# sensors.net
KiCad netlist of a schematic drawn in EAGLE
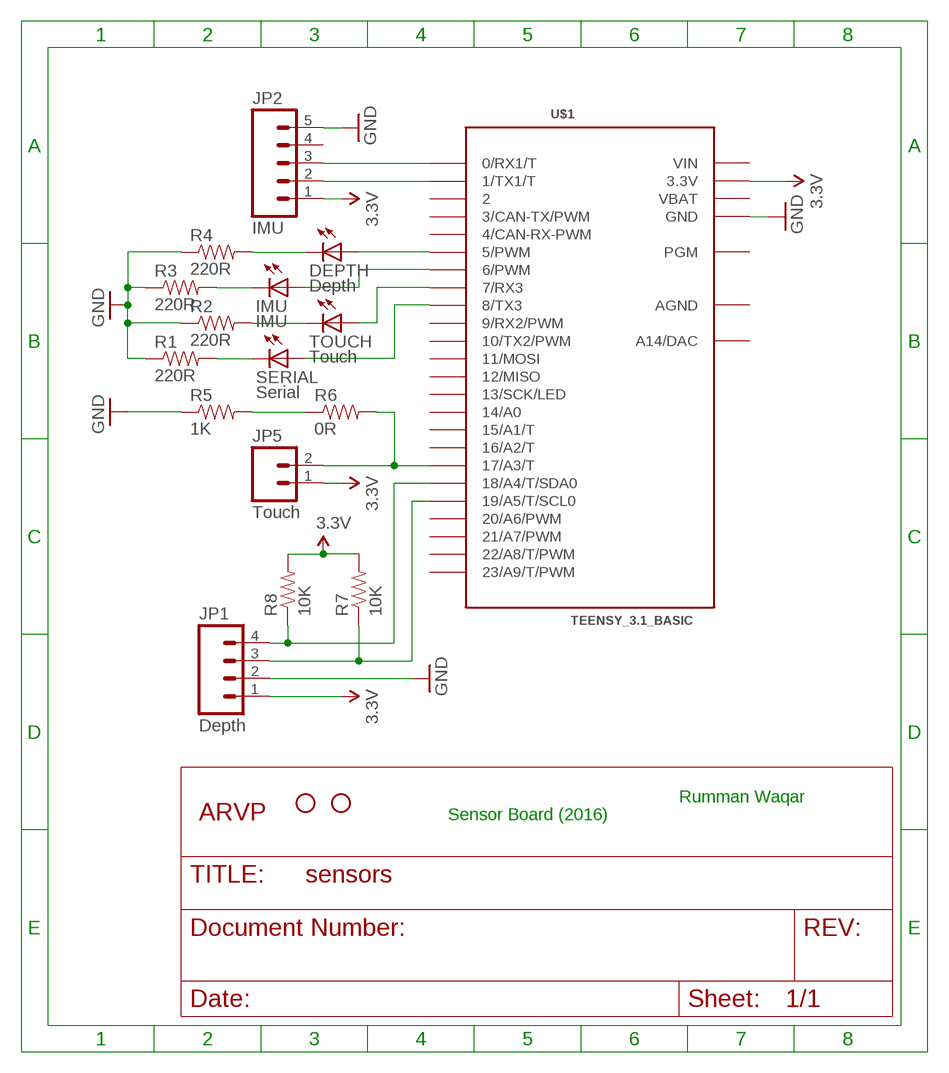
[diagram p0: schematic, sheet 1]

(export (version "E")
  (design (tool "Eeschema 10.0.6"))
  (components
    (comp (ref "DEPTH")
      (value "Depth")
      (footprint "eagle-import:LED-1206")
      (libsource (lib "eagle-import") (part "LED1206"))
    )
    (comp (ref "IMU")
      (value "IMU")
      (footprint "eagle-import:LED-1206")
      (libsource (lib "eagle-import") (part "LED1206"))
    )
    (comp (ref "JP1")
      (value "Depth")
      (footprint "eagle-import:1X04_LONGPADS")
      (libsource (lib "eagle-import") (part "M04LONGPADS"))
    )
    (comp (ref "JP2")
      (value "IMU")
      (footprint "eagle-import:1X05_LONGPADS")
      (libsource (lib "eagle-import") (part "M05PTH_LONGPADS"))
    )
    (comp (ref "JP3")
      (value "STAND-OFF")
      (footprint "eagle-import:STAND-OFF")
      (libsource (lib "eagle-import") (part "STAND-OFF"))
    )
    (comp (ref "JP4")
      (value "STAND-OFF")
      (footprint "eagle-import:STAND-OFF")
      (libsource (lib "eagle-import") (part "STAND-OFF"))
    )
    (comp (ref "JP5")
      (value "Touch")
      (footprint "eagle-import:MOLEX-1X2")
      (libsource (lib "eagle-import") (part "M02POLAR"))
    )
    (comp (ref "R1")
      (value "220R")
      (footprint "eagle-import:1206")
      (libsource (lib "eagle-import") (part "RESISTOR1206"))
    )
    (comp (ref "R2")
      (value "220R")
      (footprint "eagle-import:1206")
      (libsource (lib "eagle-import") (part "RESISTOR1206"))
    )
    (comp (ref "R3")
      (value "220R")
      (footprint "eagle-import:1206")
      (libsource (lib "eagle-import") (part "RESISTOR1206"))
    )
    (comp (ref "R4")
      (value "220R")
      (footprint "eagle-import:1206")
      (libsource (lib "eagle-import") (part "RESISTOR1206"))
    )
    (comp (ref "R5")
      (value "1K")
      (footprint "eagle-import:1206")
      (libsource (lib "eagle-import") (part "RESISTOR1206"))
    )
    (comp (ref "R6")
      (value "0R")
      (footprint "eagle-import:1206")
      (libsource (lib "eagle-import") (part "RESISTOR1206"))
    )
    (comp (ref "R7")
      (value "10K")
      (footprint "eagle-import:0805")
      (libsource (lib "eagle-import") (part "RESISTOR0805-RES"))
    )
    (comp (ref "R8")
      (value "10K")
      (footprint "eagle-import:0805")
      (libsource (lib "eagle-import") (part "RESISTOR0805-RES"))
    )
    (comp (ref "SERIAL")
      (value "Serial")
      (footprint "eagle-import:LED-1206")
      (libsource (lib "eagle-import") (part "LED1206"))
    )
    (comp (ref "TOUCH")
      (value "Touch")
      (footprint "eagle-import:LED-1206")
      (libsource (lib "eagle-import") (part "LED1206"))
    )
    (comp (ref "U$1")
      (value "TEENSY_3.1_BASIC")
      (footprint "eagle-import:TEENSY_3.1_BASIC")
      (libsource (lib "eagle-import") (part "TEENSY_3.1_BASIC"))
    )
    (comp (ref "U$2")
      (value "ARVP_LOGO")
      (footprint "eagle-import:ARVP")
      (libsource (lib "eagle-import") (part "ARVP_LOGO"))
    )
  )
  (nets
    (net (code "1") (name "/AGND") (class "Default")
      (node (ref "U$1") (pin "AGND") (pinfunction "AGND_AGND") (pintype "power_in"))
    )
    (net (code "2") (name "/VBAT") (class "Default")
      (node (ref "U$1") (pin "VBAT") (pinfunction "VBAT_VBAT") (pintype "power_in"))
    )
    (net (code "3") (name "/VIN") (class "Default")
      (node (ref "U$1") (pin "VIN") (pinfunction "VIN_VIN") (pintype "power_in"))
    )
    (net (code "4") (name "3.3V") (class "Default")
      (node (ref "JP1") (pin "1") (pinfunction "1_1") (pintype "passive"))
      (node (ref "JP2") (pin "1") (pinfunction "1_1") (pintype "passive"))
      (node (ref "JP5") (pin "1") (pinfunction "1_1") (pintype "passive"))
      (node (ref "R7") (pin "2") (pinfunction "2_2") (pintype "passive"))
      (node (ref "R8") (pin "2") (pinfunction "2_2") (pintype "passive"))
      (node (ref "U$1") (pin "3.3V") (pinfunction "3.3V_3.3V") (pintype "power_in"))
      (node (ref "U$1") (pin "3.3V1") (pinfunction "3.3V_3.3V1") (pintype "power_in"))
    )
    (net (code "5") (name "GND") (class "Default")
      (node (ref "JP1") (pin "2") (pinfunction "2_2") (pintype "passive"))
      (node (ref "JP2") (pin "5") (pinfunction "5_5") (pintype "passive"))
      (node (ref "R1") (pin "1") (pinfunction "1_1") (pintype "passive"))
      (node (ref "R2") (pin "1") (pinfunction "1_1") (pintype "passive"))
      (node (ref "R3") (pin "1") (pinfunction "1_1") (pintype "passive"))
      (node (ref "R4") (pin "1") (pinfunction "1_1") (pintype "passive"))
      (node (ref "R5") (pin "1") (pinfunction "1_1") (pintype "passive"))
      (node (ref "U$1") (pin "GND") (pinfunction "GND_GND") (pintype "power_in"))
      (node (ref "U$1") (pin "GND1") (pinfunction "GND_GND1") (pintype "power_in"))
    )
    (net (code "6") (name "Net-(DEPTH-PadC)") (class "Default")
      (node (ref "DEPTH") (pin "C") (pinfunction "C_C") (pintype "passive"))
      (node (ref "R4") (pin "2") (pinfunction "2_2") (pintype "passive"))
    )
    (net (code "7") (name "Net-(IMU-PadC)") (class "Default")
      (node (ref "IMU") (pin "C") (pinfunction "C_C") (pintype "passive"))
      (node (ref "R3") (pin "2") (pinfunction "2_2") (pintype "passive"))
    )
    (net (code "8") (name "Net-(R1-Pad2)") (class "Default")
      (node (ref "R1") (pin "2") (pinfunction "2_2") (pintype "passive"))
      (node (ref "SERIAL") (pin "C") (pinfunction "C_C") (pintype "passive"))
    )
    (net (code "9") (name "Net-(R2-Pad2)") (class "Default")
      (node (ref "R2") (pin "2") (pinfunction "2_2") (pintype "passive"))
      (node (ref "TOUCH") (pin "C") (pinfunction "C_C") (pintype "passive"))
    )
    (net (code "10") (name "Net-(R5-Pad2)") (class "Default")
      (node (ref "R5") (pin "2") (pinfunction "2_2") (pintype "passive"))
      (node (ref "R6") (pin "1") (pinfunction "1_1") (pintype "passive"))
    )
    (net (code "11") (name "Net-(U$1-0{slash}RX1{slash}T)") (class "Default")
      (node (ref "JP2") (pin "3") (pinfunction "3_3") (pintype "passive"))
      (node (ref "U$1") (pin "0") (pinfunction "0/RX1/T_0") (pintype "bidirectional"))
    )
    (net (code "12") (name "Net-(U$1-1{slash}TX1{slash}T)") (class "Default")
      (node (ref "JP2") (pin "2") (pinfunction "2_2") (pintype "passive"))
      (node (ref "U$1") (pin "1") (pinfunction "1/TX1/T_1") (pintype "bidirectional"))
    )
    (net (code "13") (name "Net-(U$1-5{slash}PWM)") (class "Default")
      (node (ref "DEPTH") (pin "A") (pinfunction "A_A") (pintype "passive"))
      (node (ref "U$1") (pin "5") (pinfunction "5/PWM_5") (pintype "bidirectional"))
    )
    (net (code "14") (name "Net-(U$1-6{slash}PWM)") (class "Default")
      (node (ref "IMU") (pin "A") (pinfunction "A_A") (pintype "passive"))
      (node (ref "U$1") (pin "6") (pinfunction "6/PWM_6") (pintype "bidirectional"))
    )
    (net (code "15") (name "Net-(U$1-7{slash}RX3)") (class "Default")
      (node (ref "TOUCH") (pin "A") (pinfunction "A_A") (pintype "passive"))
      (node (ref "U$1") (pin "7") (pinfunction "7/RX3_7") (pintype "bidirectional"))
    )
    (net (code "16") (name "Net-(U$1-8{slash}TX3)") (class "Default")
      (node (ref "SERIAL") (pin "A") (pinfunction "A_A") (pintype "passive"))
      (node (ref "U$1") (pin "8") (pinfunction "8/TX3_8") (pintype "bidirectional"))
    )
    (net (code "17") (name "Net-(U$1-17{slash}A3{slash}T)") (class "Default")
      (node (ref "JP5") (pin "2") (pinfunction "2_2") (pintype "passive"))
      (node (ref "R6") (pin "2") (pinfunction "2_2") (pintype "passive"))
      (node (ref "U$1") (pin "17/A3") (pinfunction "17/A3/T_17/A3") (pintype "bidirectional"))
    )
    (net (code "18") (name "Net-(U$1-18{slash}A4{slash}T{slash}SDA0)") (class "Default")
      (node (ref "JP1") (pin "4") (pinfunction "4_4") (pintype "passive"))
      (node (ref "R8") (pin "1") (pinfunction "1_1") (pintype "passive"))
      (node (ref "U$1") (pin "18/A4") (pinfunction "18/A4/T/SDA0_18/A4") (pintype "bidirectional"))
    )
    (net (code "19") (name "Net-(U$1-19{slash}A5{slash}T{slash}SCL0)") (class "Default")
      (node (ref "JP1") (pin "3") (pinfunction "3_3") (pintype "passive"))
      (node (ref "R7") (pin "1") (pinfunction "1_1") (pintype "passive"))
      (node (ref "U$1") (pin "19/A5") (pinfunction "19/A5/T/SCL0_19/A5") (pintype "bidirectional"))
    )
    (net (code "20") (name "unconnected-(JP2-Pad4)") (class "Default")
      (node (ref "JP2") (pin "4") (pinfunction "4_4") (pintype "passive"))
    )
    (net (code "21") (name "unconnected-(U$1-3{slash}CAN-TX{slash}PWM-Pad3)") (class "Default")
      (node (ref "U$1") (pin "3") (pinfunction "3/CAN-TX/PWM_3") (pintype "bidirectional"))
    )
    (net (code "22") (name "unconnected-(U$1-4{slash}CAN-RX-PWM-Pad4)") (class "Default")
      (node (ref "U$1") (pin "4") (pinfunction "4/CAN-RX-PWM_4") (pintype "bidirectional"))
    )
    (net (code "23") (name "unconnected-(U$1-9{slash}RX2{slash}PWM-Pad9)") (class "Default")
      (node (ref "U$1") (pin "9") (pinfunction "9/RX2/PWM_9") (pintype "bidirectional"))
    )
    (net (code "24") (name "unconnected-(U$1-10{slash}TX2{slash}PWM-Pad10)") (class "Default")
      (node (ref "U$1") (pin "10") (pinfunction "10/TX2/PWM_10") (pintype "bidirectional"))
    )
    (net (code "25") (name "unconnected-(U$1-11{slash}MOSI-Pad11)") (class "Default")
      (node (ref "U$1") (pin "11") (pinfunction "11/MOSI_11") (pintype "bidirectional"))
    )
    (net (code "26") (name "unconnected-(U$1-12{slash}MISO-Pad12)") (class "Default")
      (node (ref "U$1") (pin "12") (pinfunction "12/MISO_12") (pintype "bidirectional"))
    )
    (net (code "27") (name "unconnected-(U$1-13{slash}SCK{slash}LED-Pad13)") (class "Default")
      (node (ref "U$1") (pin "13") (pinfunction "13/SCK/LED_13") (pintype "bidirectional"))
    )
    (net (code "28") (name "unconnected-(U$1-15{slash}A1{slash}T-Pad15{slash}A1)") (class "Default")
      (node (ref "U$1") (pin "15/A1") (pinfunction "15/A1/T_15/A1") (pintype "bidirectional"))
    )
    (net (code "29") (name "unconnected-(U$1-16{slash}A2{slash}T-Pad16{slash}A2)") (class "Default")
      (node (ref "U$1") (pin "16/A2") (pinfunction "16/A2/T_16/A2") (pintype "bidirectional"))
    )
    (net (code "30") (name "unconnected-(U$1-20{slash}A6{slash}PWM-Pad20{slash}A6)") (class "Default")
      (node (ref "U$1") (pin "20/A6") (pinfunction "20/A6/PWM_20/A6") (pintype "bidirectional"))
    )
    (net (code "31") (name "unconnected-(U$1-21{slash}A7{slash}PWM-Pad21{slash}A7)") (class "Default")
      (node (ref "U$1") (pin "21/A7") (pinfunction "21/A7/PWM_21/A7") (pintype "bidirectional"))
    )
    (net (code "32") (name "unconnected-(U$1-22{slash}A8{slash}T{slash}PWM-Pad22{slash}A8)") (class "Default")
      (node (ref "U$1") (pin "22/A8") (pinfunction "22/A8/T/PWM_22/A8") (pintype "bidirectional"))
    )
    (net (code "33") (name "unconnected-(U$1-23{slash}A9{slash}T{slash}PWM-Pad23{slash}A9)") (class "Default")
      (node (ref "U$1") (pin "23/A9") (pinfunction "23/A9/T/PWM_23/A9") (pintype "bidirectional"))
    )
    (net (code "34") (name "unconnected-(U$1-A14{slash}DAC-PadA14)") (class "Default")
      (node (ref "U$1") (pin "A14") (pinfunction "A14/DAC_A14") (pintype "bidirectional"))
    )
    (net (code "35") (name "unconnected-(U$1-Pad2)") (class "Default")
      (node (ref "U$1") (pin "2") (pinfunction "2_2") (pintype "bidirectional"))
    )
    (net (code "36") (name "unconnected-(U$1-Pad14{slash}A0)") (class "Default")
      (node (ref "U$1") (pin "14/A0") (pinfunction "14/A0_14/A0") (pintype "bidirectional"))
    )
    (net (code "37") (name "unconnected-(U$1-PadPGM)") (class "Default")
      (node (ref "U$1") (pin "PGM") (pinfunction "PGM_PGM") (pintype "bidirectional"))
    )
  )
)
